# constantCV.net
KiCad netlist of a schematic drawn in Altium Designer
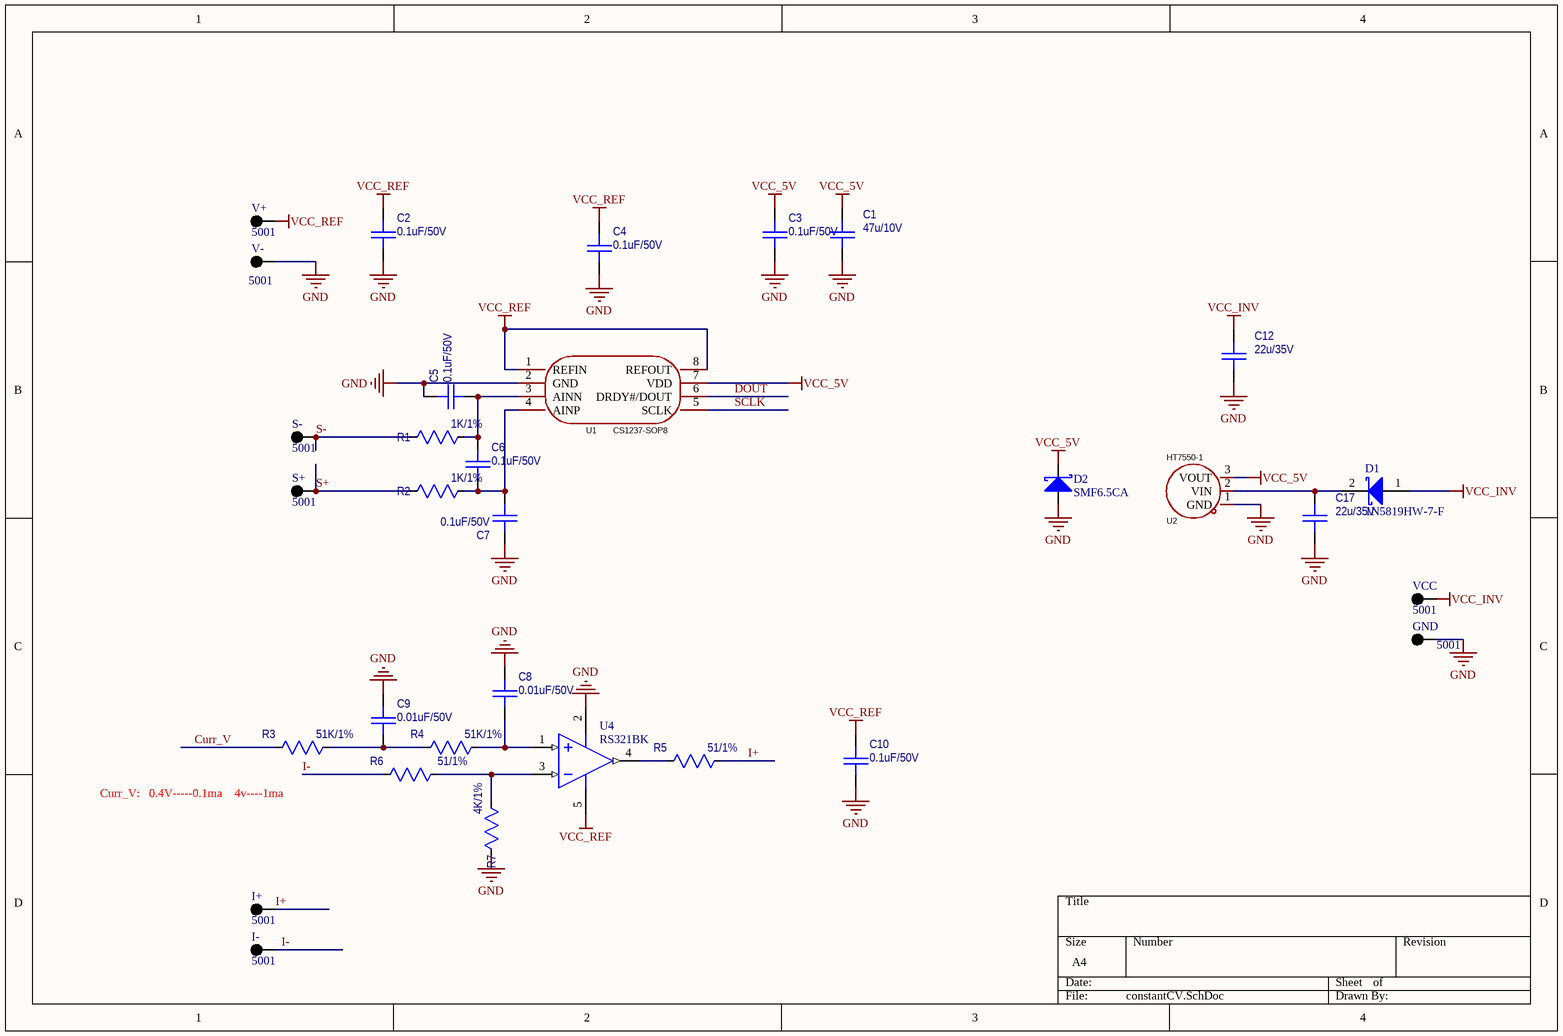
[diagram p0: constantCV.SchDoc]

(export (version "E")
  (design (tool "Eeschema 10.0.6"))
  (components
    (comp (ref "C1")
      (value "47u/10V")
      (footprint "CAPC2012X127N_0805")
      (description "Capacitor, MLCC")
      (fields (field (name "MANUFACTURER") "KEMET") (field (name "PARTNUMBER") "C0805C106K8PACTU"))
      (libsource (lib "Karl") (part "Capacitor_0805"))
    )
    (comp (ref "C2")
      (value "0.1uF/50V")
      (footprint "CAPC1608X092N_0603")
      (description "Capacitor, MLCC")
      (fields (field (name "MANUFACTURER") "KEMET") (field (name "PARTNUMBER") "C0603C104M5RACTU"))
      (libsource (lib "Karl") (part "Capacitor_0603"))
    )
    (comp (ref "C3")
      (value "0.1uF/50V")
      (footprint "CAPC1608X092N_0603")
      (description "Capacitor, MLCC")
      (fields (field (name "MANUFACTURER") "KEMET") (field (name "PARTNUMBER") "C0603C104M5RACTU"))
      (libsource (lib "Karl") (part "Capacitor_0603"))
    )
    (comp (ref "C4")
      (value "0.1uF/50V")
      (footprint "CAPC1608X092N_0603")
      (description "Capacitor, MLCC")
      (fields (field (name "MANUFACTURER") "KEMET") (field (name "PARTNUMBER") "C0603C104M5RACTU"))
      (libsource (lib "Karl") (part "Capacitor_0603"))
    )
    (comp (ref "C5")
      (value "0.1uF/50V")
      (footprint "CAPC1608X092N_0603")
      (description "Capacitor, MLCC")
      (fields (field (name "MANUFACTURER") "KEMET") (field (name "PARTNUMBER") "C0603C104M5RACTU"))
      (libsource (lib "Karl") (part "Capacitor_0603"))
    )
    (comp (ref "C6")
      (value "0.1uF/50V")
      (footprint "CAPC1608X092N_0603")
      (description "Capacitor, MLCC")
      (fields (field (name "MANUFACTURER") "KEMET") (field (name "PARTNUMBER") "C0603C104M5RACTU"))
      (libsource (lib "Karl") (part "Capacitor_0603"))
    )
    (comp (ref "C7")
      (value "0.1uF/50V")
      (footprint "CAPC1608X092N_0603")
      (description "Capacitor, MLCC")
      (fields (field (name "MANUFACTURER") "KEMET") (field (name "PARTNUMBER") "C0603C104M5RACTU"))
      (libsource (lib "Karl") (part "Capacitor_0603"))
    )
    (comp (ref "C8")
      (value "0.01uF/50V")
      (footprint "CAPC1608X092N_0603")
      (description "Capacitor, MLCC")
      (fields (field (name "MANUFACTURER") "KEMET") (field (name "PARTNUMBER") "C0603C104M5RACTU"))
      (libsource (lib "Karl") (part "Capacitor_0603"))
    )
    (comp (ref "C9")
      (value "0.01uF/50V")
      (footprint "CAPC1608X092N_0603")
      (description "Capacitor, MLCC")
      (fields (field (name "MANUFACTURER") "KEMET") (field (name "PARTNUMBER") "C0603C104M5RACTU"))
      (libsource (lib "Karl") (part "Capacitor_0603"))
    )
    (comp (ref "C10")
      (value "0.1uF/50V")
      (footprint "CAPC1608X092N_0603")
      (description "Capacitor, MLCC")
      (fields (field (name "MANUFACTURER") "KEMET") (field (name "PARTNUMBER") "C0603C104M5RACTU"))
      (libsource (lib "Karl") (part "Capacitor_0603"))
    )
    (comp (ref "C12")
      (value "22u/35V")
      (footprint "CAPC2012X127N_0805")
      (description "Capacitor, MLCC")
      (fields (field (name "MANUFACTURER") "KEMET") (field (name "PARTNUMBER") "C0805C106K8PACTU"))
      (libsource (lib "Karl") (part "Capacitor_0805"))
    )
    (comp (ref "C17")
      (value "22u/35V")
      (footprint "CAPC2012X127N_0805")
      (description "Capacitor, MLCC")
      (fields (field (name "MANUFACTURER") "KEMET") (field (name "PARTNUMBER") "C0805C106K8PACTU"))
      (libsource (lib "Karl") (part "Capacitor_0805"))
    )
    (comp (ref "D1")
      (value "1N5819HW-7-F")
      (footprint "DIOD-SOD-123-2_V")
      (libsource (lib "Bogen") (part "1N5819HW-7-F"))
    )
    (comp (ref "D2") (value "SMF6.5CA") (footprint "SOD123") (libsource (lib "*") (part "DIODE S")))
    (comp (ref "GND")
      (value "5001")
      (footprint "KSTN-5001")
      (description "Test Point, Black, 1-Pin THD, RoHS, Bulk")
      (fields (field (name "MANUFACTURER") "Keystone"))
      (libsource (lib "Bogen") (part "5001"))
    )
    (comp (ref "I+")
      (value "5001")
      (footprint "KSTN-5001")
      (description "Test Point, Black, 1-Pin THD, RoHS, Bulk")
      (fields (field (name "MANUFACTURER") "Keystone"))
      (libsource (lib "Bogen") (part "5001"))
    )
    (comp (ref "I-")
      (value "5001")
      (footprint "KSTN-5001")
      (description "Test Point, Black, 1-Pin THD, RoHS, Bulk")
      (fields (field (name "MANUFACTURER") "Keystone"))
      (libsource (lib "Bogen") (part "5001"))
    )
    (comp (ref "R1")
      (value "1K/1%")
      (footprint "RESC1608X055N_0603")
      (description "Resistor, Standard")
      (fields (field (name "MANUFACTURER") "Yageo") (field (name "PARTNUMBER") "RC0603FR-1075KL"))
      (libsource (lib "Karl") (part "Resistor_0603"))
    )
    (comp (ref "R2")
      (value "1K/1%")
      (footprint "RESC1608X055N_0603")
      (description "Resistor, Standard")
      (fields (field (name "MANUFACTURER") "Yageo") (field (name "PARTNUMBER") "RC0603FR-1075KL"))
      (libsource (lib "Karl") (part "Resistor_0603"))
    )
    (comp (ref "R3")
      (value "51K/1%")
      (footprint "RESC1608X055N_0603")
      (description "Resistor, Standard")
      (fields (field (name "MANUFACTURER") "Yageo") (field (name "PARTNUMBER") "RC0603FR-1075KL"))
      (libsource (lib "Karl") (part "Resistor_0603"))
    )
    (comp (ref "R4")
      (value "51K/1%")
      (footprint "RESC1608X055N_0603")
      (description "Resistor, Standard")
      (fields (field (name "MANUFACTURER") "Yageo") (field (name "PARTNUMBER") "RC0603FR-1075KL"))
      (libsource (lib "Karl") (part "Resistor_0603"))
    )
    (comp (ref "R5")
      (value "51/1%")
      (footprint "RESC1608X055N_0603")
      (description "Resistor, Standard")
      (fields (field (name "MANUFACTURER") "Yageo") (field (name "PARTNUMBER") "RC0603FR-1075KL"))
      (libsource (lib "Karl") (part "Resistor_0603"))
    )
    (comp (ref "R6")
      (value "51/1%")
      (footprint "RESC1608X055N_0603")
      (description "Resistor, Standard")
      (fields (field (name "MANUFACTURER") "Yageo") (field (name "PARTNUMBER") "RC0603FR-1075KL"))
      (libsource (lib "Karl") (part "Resistor_0603"))
    )
    (comp (ref "R7")
      (value "4K/1%")
      (footprint "RESC1608X055N_0603")
      (description "Resistor, Standard")
      (fields (field (name "MANUFACTURER") "Yageo") (field (name "PARTNUMBER") "RC0603FR-1075KL"))
      (libsource (lib "Karl") (part "Resistor_0603"))
    )
    (comp (ref "S+")
      (value "5001")
      (footprint "KSTN-5001")
      (description "Test Point, Black, 1-Pin THD, RoHS, Bulk")
      (fields (field (name "MANUFACTURER") "Keystone"))
      (libsource (lib "Bogen") (part "5001"))
    )
    (comp (ref "S-")
      (value "5001")
      (footprint "KSTN-5001")
      (description "Test Point, Black, 1-Pin THD, RoHS, Bulk")
      (fields (field (name "MANUFACTURER") "Keystone"))
      (libsource (lib "Bogen") (part "5001"))
    )
    (comp (ref "U1")
      (value "CS1237-SOP8")
      (footprint "SOIC-8_L5.0-W4.0-P1.27-LS6.0-BL:SOIC-8_L5.0-W4.0-P1.27-LS6.0-BL")
      (fields (field (name "MANUFACTURER") "CHIPSEA(芯海科技)"))
      (libsource (lib "altium-import") (part "root_0_CS1237-SOP8_"))
    )
    (comp (ref "U2")
      (value "HT7550-1")
      (footprint "SOT-89_L4.5-W2.5-P1.50-LS4.2-BR:SOT-89_L4.5-W2.5-P1.50-LS4.2-BR")
      (fields (field (name "MANUFACTURER") "UMW(友台半导体)"))
      (libsource (lib "altium-import") (part "root_2_HT7550-1_C347189_"))
    )
    (comp (ref "U4")
      (value "RS321BK")
      (footprint "SHBL-SOT-23-5_N")
      (fields
        (field (name "MANUFACTURER") "Shanghai Belling")
        (field (name "PARTNUMBER") "BL321LFR")
        (field (name "PUBLISHER") "Bolgen Studio")
      )
      (libsource (lib "Bogen") (part "BL321LFR"))
    )
    (comp (ref "V+")
      (value "5001")
      (footprint "KSTN-5001")
      (description "Test Point, Black, 1-Pin THD, RoHS, Bulk")
      (fields (field (name "MANUFACTURER") "Keystone"))
      (libsource (lib "Bogen") (part "5001"))
    )
    (comp (ref "V-")
      (value "5001")
      (footprint "KSTN-5001")
      (description "Test Point, Black, 1-Pin THD, RoHS, Bulk")
      (fields (field (name "MANUFACTURER") "Keystone"))
      (libsource (lib "Bogen") (part "5001"))
    )
    (comp (ref "VCC")
      (value "5001")
      (footprint "KSTN-5001")
      (description "Test Point, Black, 1-Pin THD, RoHS, Bulk")
      (fields (field (name "MANUFACTURER") "Keystone"))
      (libsource (lib "Bogen") (part "5001"))
    )
  )
  (nets
    (net (code "1") (name "/Curr_V") (class "Default")
      (node (ref "R3") (pin "2") (pinfunction "2_2") (pintype "passive"))
    )
    (net (code "2") (name "/DOUT") (class "Default")
      (node (ref "U1") (pin "6") (pinfunction "DRDY#/DOUT_6") (pintype "passive"))
    )
    (net (code "3") (name "/I+") (class "Default")
      (node (ref "I+") (pin "1") (pintype "passive"))
      (node (ref "R5") (pin "1") (pinfunction "1_1") (pintype "passive"))
    )
    (net (code "4") (name "/I-") (class "Default")
      (node (ref "I-") (pin "1") (pintype "passive"))
      (node (ref "R6") (pin "2") (pinfunction "2_2") (pintype "passive"))
    )
    (net (code "5") (name "/S+") (class "Default")
      (node (ref "R2") (pin "2") (pinfunction "2_2") (pintype "passive"))
      (node (ref "S+") (pin "1") (pintype "passive"))
    )
    (net (code "6") (name "/S-") (class "Default")
      (node (ref "R1") (pin "2") (pinfunction "2_2") (pintype "passive"))
      (node (ref "S-") (pin "1") (pintype "passive"))
    )
    (net (code "7") (name "/SCLK") (class "Default")
      (node (ref "U1") (pin "5") (pinfunction "SCLK_5") (pintype "passive"))
    )
    (net (code "8") (name "GND") (class "Default")
      (node (ref "C1") (pin "2") (pinfunction "2_2") (pintype "passive"))
      (node (ref "C10") (pin "2") (pinfunction "2_2") (pintype "passive"))
      (node (ref "C12") (pin "2") (pinfunction "2_2") (pintype "passive"))
      (node (ref "C17") (pin "2") (pinfunction "2_2") (pintype "passive"))
      (node (ref "C2") (pin "2") (pinfunction "2_2") (pintype "passive"))
      (node (ref "C3") (pin "2") (pinfunction "2_2") (pintype "passive"))
      (node (ref "C4") (pin "2") (pinfunction "2_2") (pintype "passive"))
      (node (ref "C5") (pin "1") (pinfunction "1_1") (pintype "passive"))
      (node (ref "C7") (pin "1") (pinfunction "1_1") (pintype "passive"))
      (node (ref "C8") (pin "1") (pinfunction "1_1") (pintype "passive"))
      (node (ref "C9") (pin "1") (pinfunction "1_1") (pintype "passive"))
      (node (ref "D2") (pin "1") (pinfunction "A_1") (pintype "passive"))
      (node (ref "GND") (pin "1") (pintype "passive"))
      (node (ref "R7") (pin "2") (pinfunction "2_2") (pintype "passive"))
      (node (ref "U1") (pin "2") (pinfunction "GND_2") (pintype "passive"))
      (node (ref "U2") (pin "1") (pinfunction "GND_1") (pintype "passive"))
      (node (ref "U4") (pin "2") (pinfunction "VSS_2") (pintype "power_in"))
      (node (ref "V-") (pin "1") (pintype "passive"))
    )
    (net (code "9") (name "Net-(C9-Pad2)") (class "Default")
      (node (ref "C9") (pin "2") (pinfunction "2_2") (pintype "passive"))
      (node (ref "R3") (pin "1") (pinfunction "1_1") (pintype "passive"))
      (node (ref "R4") (pin "2") (pinfunction "2_2") (pintype "passive"))
    )
    (net (code "10") (name "Net-(D1-K)") (class "Default")
      (node (ref "C17") (pin "1") (pinfunction "1_1") (pintype "passive"))
      (node (ref "D1") (pin "2") (pinfunction "K_2") (pintype "passive"))
      (node (ref "U2") (pin "2") (pinfunction "VIN_2") (pintype "passive"))
    )
    (net (code "11") (name "Net-(U1-AINN)") (class "Default")
      (node (ref "C5") (pin "2") (pinfunction "2_2") (pintype "passive"))
      (node (ref "C6") (pin "1") (pinfunction "1_1") (pintype "passive"))
      (node (ref "R1") (pin "1") (pinfunction "1_1") (pintype "passive"))
      (node (ref "U1") (pin "3") (pinfunction "AINN_3") (pintype "passive"))
    )
    (net (code "12") (name "Net-(U1-AINP)") (class "Default")
      (node (ref "C6") (pin "2") (pinfunction "2_2") (pintype "passive"))
      (node (ref "C7") (pin "2") (pinfunction "2_2") (pintype "passive"))
      (node (ref "R2") (pin "1") (pinfunction "1_1") (pintype "passive"))
      (node (ref "U1") (pin "4") (pinfunction "AINP_4") (pintype "passive"))
    )
    (net (code "13") (name "Net-(U4-IN+)") (class "Default")
      (node (ref "C8") (pin "2") (pinfunction "2_2") (pintype "passive"))
      (node (ref "R4") (pin "1") (pinfunction "1_1") (pintype "passive"))
      (node (ref "U4") (pin "1") (pinfunction "IN+_1") (pintype "input"))
    )
    (net (code "14") (name "Net-(U4-IN-)") (class "Default")
      (node (ref "R6") (pin "1") (pinfunction "1_1") (pintype "passive"))
      (node (ref "R7") (pin "1") (pinfunction "1_1") (pintype "passive"))
      (node (ref "U4") (pin "3") (pinfunction "IN-_3") (pintype "input"))
    )
    (net (code "15") (name "Net-(U4-OUT)") (class "Default")
      (node (ref "R5") (pin "2") (pinfunction "2_2") (pintype "passive"))
      (node (ref "U4") (pin "4") (pinfunction "OUT_4") (pintype "output"))
    )
    (net (code "16") (name "VCC_5V") (class "Default")
      (node (ref "C1") (pin "1") (pinfunction "1_1") (pintype "passive"))
      (node (ref "C3") (pin "1") (pinfunction "1_1") (pintype "passive"))
      (node (ref "D2") (pin "2") (pinfunction "K_2") (pintype "passive"))
      (node (ref "U1") (pin "7") (pinfunction "VDD_7") (pintype "passive"))
      (node (ref "U2") (pin "3") (pinfunction "VOUT_3") (pintype "passive"))
    )
    (net (code "17") (name "VCC_INV") (class "Default")
      (node (ref "C12") (pin "1") (pinfunction "1_1") (pintype "passive"))
      (node (ref "D1") (pin "1") (pinfunction "A_1") (pintype "passive"))
      (node (ref "VCC") (pin "1") (pintype "passive"))
    )
    (net (code "18") (name "VCC_REF") (class "Default")
      (node (ref "C10") (pin "1") (pinfunction "1_1") (pintype "passive"))
      (node (ref "C2") (pin "1") (pinfunction "1_1") (pintype "passive"))
      (node (ref "C4") (pin "1") (pinfunction "1_1") (pintype "passive"))
      (node (ref "U1") (pin "1") (pinfunction "REFIN_1") (pintype "passive"))
      (node (ref "U1") (pin "8") (pinfunction "REFOUT_8") (pintype "passive"))
      (node (ref "U4") (pin "5") (pinfunction "VDD_5") (pintype "power_in"))
      (node (ref "V+") (pin "1") (pintype "passive"))
    )
  )
)
